# untitled.net
KiCad netlist of a schematic drawn in EAGLE
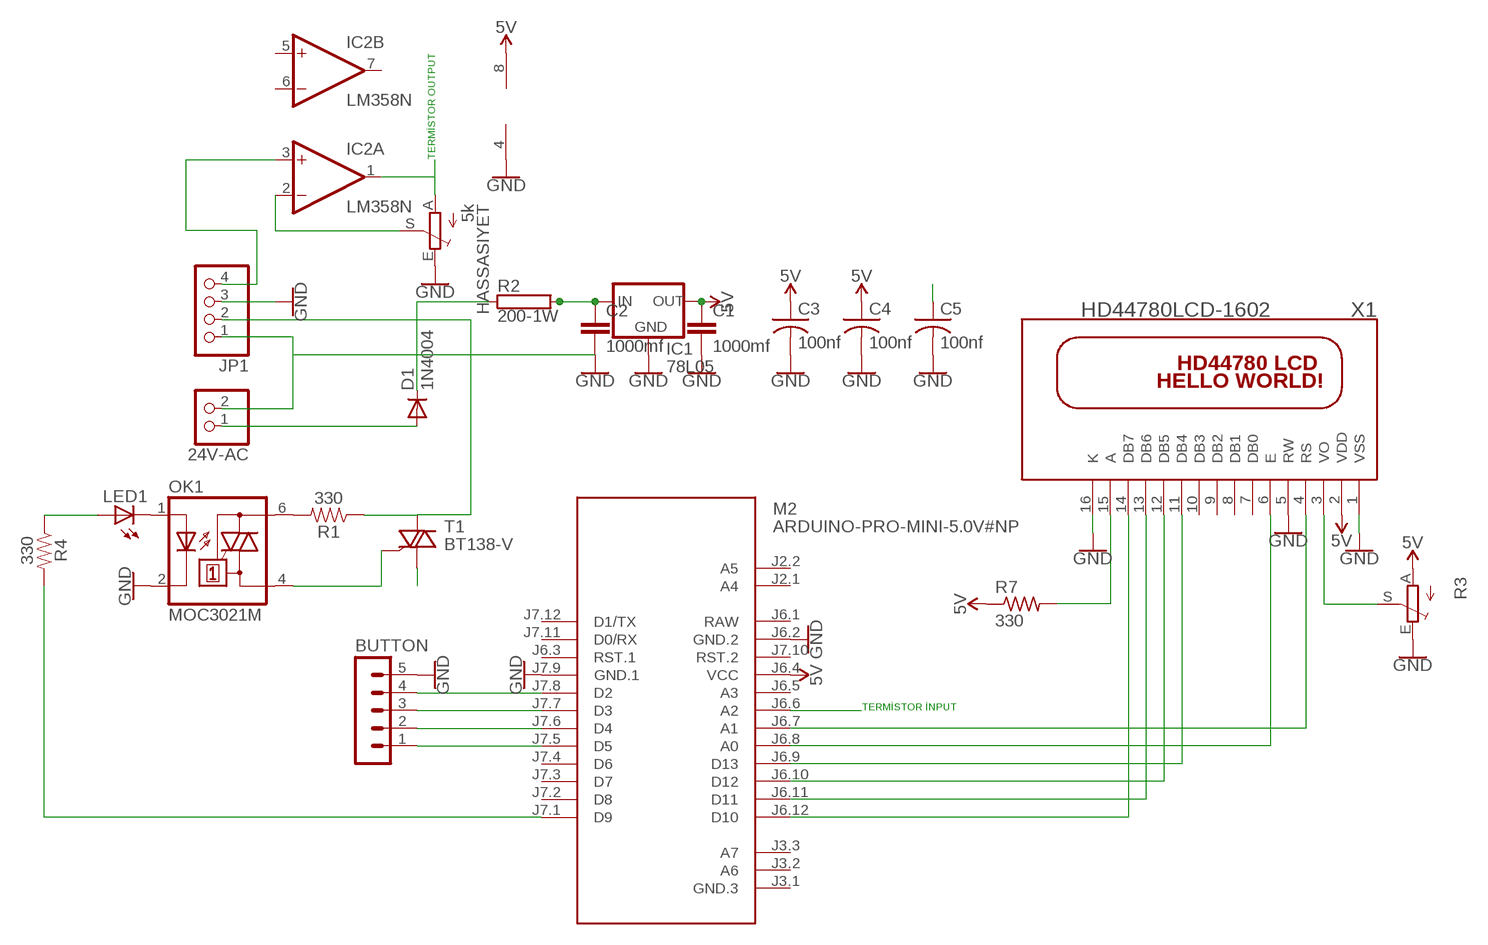
[diagram p0: schematic, sheet 1]

(export (version "E")
  (design (tool "Eeschema 10.0.6"))
  (components
    (comp (ref "24V-AC")
      (value "PINHD-1X2")
      (footprint "eagle-import:1X02")
      (libsource (lib "eagle-import") (part "PINHD-1X2"))
    )
    (comp (ref "BUTTON")
      (value "MA05-1")
      (footprint "eagle-import:MA05-1")
      (libsource (lib "eagle-import") (part "MA05-1"))
    )
    (comp (ref "C1")
      (value "1000mf")
      (footprint "eagle-import:C5B3.5")
      (libsource (lib "eagle-import") (part "C5/3.5"))
    )
    (comp (ref "C2")
      (value "1000mf")
      (footprint "eagle-import:C5B3.5")
      (libsource (lib "eagle-import") (part "C5/3.5"))
    )
    (comp (ref "C3")
      (value "100nf")
      (footprint "eagle-import:C1206")
      (libsource (lib "eagle-import") (part "C-USC1206"))
    )
    (comp (ref "C4")
      (value "100nf")
      (footprint "eagle-import:C1206")
      (libsource (lib "eagle-import") (part "C-USC1206"))
    )
    (comp (ref "C5")
      (value "100nf")
      (footprint "eagle-import:C1206")
      (libsource (lib "eagle-import") (part "C-USC1206"))
    )
    (comp (ref "D1")
      (value "1N4004")
      (footprint "eagle-import:DO41-10")
      (libsource (lib "eagle-import") (part "1N4004"))
    )
    (comp (ref "HASSASIYET")
      (value "5k")
      (footprint "eagle-import:S64W")
      (libsource (lib "eagle-import") (part "TRIM_EU-S64W"))
    )
    (comp (ref "IC1")
      (value "78L05")
      (footprint "eagle-import:78MXXS")
      (libsource (lib "eagle-import") (part "78MXXS"))
    )
    (comp (ref "IC2")
      (value "LM358N")
      (footprint "eagle-import:DIL08")
      (libsource (lib "eagle-import") (part "LM358N"))
    )
    (comp (ref "JP1")
      (value "PINHD-1X4")
      (footprint "eagle-import:1X04")
      (libsource (lib "eagle-import") (part "PINHD-1X4"))
    )
    (comp (ref "LED1")
      (value "LED3MM")
      (footprint "eagle-import:LED3MM")
      (libsource (lib "eagle-import") (part "LED3MM"))
    )
    (comp (ref "M2")
      (value "ARDUINO-PRO-MINI-5.0V#NP")
      (footprint "eagle-import:ARDUINO-PRO-MINI#NP")
      (libsource (lib "eagle-import") (part "ARDUINO-PRO-MINI-#NP5.0V"))
    )
    (comp (ref "OK1")
      (value "MOC3021M")
      (footprint "eagle-import:DIL06")
      (fields (field (name "MF") "FAIRCHILD SEMICONDUCTOR") (field (name "MPN") "MOC3021-M"))
      (libsource (lib "eagle-import") (part "MOC30M21"))
    )
    (comp (ref "R1")
      (value "330")
      (footprint "eagle-import:AXIAL-0.3")
      (libsource (lib "eagle-import") (part "1KOHM-HORIZ-1/4W-1%"))
    )
    (comp (ref "R2")
      (value "200-1W")
      (footprint "eagle-import:KH206-8R")
      (libsource (lib "eagle-import") (part "RKH206-8R"))
    )
    (comp (ref "R3")
      (value "TRIM_EU-CA6V")
      (footprint "eagle-import:CA6V")
      (libsource (lib "eagle-import") (part "TRIM_EU-CA6V"))
    )
    (comp (ref "R4")
      (value "330")
      (footprint "eagle-import:AXIAL-0.3")
      (libsource (lib "eagle-import") (part "1KOHM-HORIZ-1/4W-1%"))
    )
    (comp (ref "R7")
      (value "330")
      (footprint "eagle-import:0207_10")
      (libsource (lib "eagle-import") (part "R-US_0207/10"))
    )
    (comp (ref "T1")
      (value "BT138-V")
      (footprint "eagle-import:TO220BV")
      (libsource (lib "eagle-import") (part "BT138-V"))
    )
    (comp (ref "X1")
      (value "HD44780LCD-1602")
      (footprint "eagle-import:LCD1602")
      (libsource (lib "eagle-import") (part "HD44780LCD-1602"))
    )
  )
  (nets
    (net (code "1") (name "/24V") (class "Default")
      (node (ref "C2") (pin "1") (pinfunction "1_1") (pintype "passive"))
      (node (ref "C5") (pin "1") (pinfunction "1_1") (pintype "passive"))
      (node (ref "IC1") (pin "IN") (pinfunction "IN_IN") (pintype "input"))
      (node (ref "R2") (pin "2") (pinfunction "2_2") (pintype "passive"))
    )
    (net (code "2") (name "/A2") (class "Default")
      (node (ref "HASSASIYET") (pin "A") (pinfunction "A_A") (pintype "passive"))
      (node (ref "IC2") (pin "1") (pinfunction "OUT_1") (pintype "output"))
      (node (ref "M2") (pin "J6.6") (pinfunction "A2_J6.6") (pintype "bidirectional"))
    )
    (net (code "3") (name "/N$24") (class "Default")
      (node (ref "24V-AC") (pin "1") (pinfunction "1_1") (pintype "passive"))
      (node (ref "D1") (pin "A") (pinfunction "A_A") (pintype "passive"))
      (node (ref "T1") (pin "T1") (pinfunction "A1_T1") (pintype "passive"))
    )
    (net (code "4") (name "/RAW") (class "Default")
      (node (ref "M2") (pin "J6.1") (pinfunction "RAW_J6.1") (pintype "power_in"))
    )
    (net (code "5") (name "5V") (class "Default")
      (node (ref "C1") (pin "1") (pinfunction "1_1") (pintype "passive"))
      (node (ref "C3") (pin "1") (pinfunction "1_1") (pintype "passive"))
      (node (ref "C4") (pin "1") (pinfunction "1_1") (pintype "passive"))
      (node (ref "IC1") (pin "OUT") (pinfunction "OUT_OUT") (pintype "passive"))
      (node (ref "IC2") (pin "8") (pinfunction "V+_8") (pintype "power_in"))
      (node (ref "M2") (pin "J6.4") (pinfunction "VCC_J6.4") (pintype "power_in"))
      (node (ref "R3") (pin "A") (pinfunction "A_A") (pintype "passive"))
      (node (ref "R7") (pin "1") (pinfunction "1_1") (pintype "passive"))
      (node (ref "X1") (pin "2") (pinfunction "VDD_2") (pintype "power_in"))
    )
    (net (code "6") (name "GND") (class "Default")
      (node (ref "24V-AC") (pin "2") (pinfunction "2_2") (pintype "passive"))
      (node (ref "BUTTON") (pin "5") (pinfunction "5_5") (pintype "passive"))
      (node (ref "C1") (pin "2") (pinfunction "2_2") (pintype "passive"))
      (node (ref "C2") (pin "2") (pinfunction "2_2") (pintype "passive"))
      (node (ref "C3") (pin "2") (pinfunction "2_2") (pintype "passive"))
      (node (ref "C4") (pin "2") (pinfunction "2_2") (pintype "passive"))
      (node (ref "C5") (pin "2") (pinfunction "2_2") (pintype "passive"))
      (node (ref "HASSASIYET") (pin "E") (pinfunction "E_E") (pintype "passive"))
      (node (ref "IC1") (pin "GND") (pinfunction "GND_GND") (pintype "input"))
      (node (ref "IC2") (pin "4") (pinfunction "V-_4") (pintype "power_in"))
      (node (ref "JP1") (pin "1") (pinfunction "1_1") (pintype "passive"))
      (node (ref "JP1") (pin "3") (pinfunction "3_3") (pintype "passive"))
      (node (ref "M2") (pin "J6.2") (pinfunction "GND.2_J6.2") (pintype "power_in"))
      (node (ref "M2") (pin "J7.9") (pinfunction "GND.1_J7.9") (pintype "power_in"))
      (node (ref "OK1") (pin "2") (pinfunction "C_2") (pintype "passive"))
      (node (ref "R3") (pin "E") (pinfunction "E_E") (pintype "passive"))
      (node (ref "X1") (pin "1") (pinfunction "VSS_1") (pintype "power_in"))
      (node (ref "X1") (pin "16") (pinfunction "K_16") (pintype "input"))
      (node (ref "X1") (pin "5") (pinfunction "RW_5") (pintype "input"))
    )
    (net (code "7") (name "Net-(D1-PadC)") (class "Default")
      (node (ref "D1") (pin "C") (pinfunction "C_C") (pintype "passive"))
      (node (ref "R2") (pin "1") (pinfunction "1_1") (pintype "passive"))
    )
    (net (code "8") (name "Net-(IC2A-+IN)") (class "Default")
      (node (ref "IC2") (pin "3") (pinfunction "+IN_3") (pintype "input"))
      (node (ref "JP1") (pin "4") (pinfunction "4_4") (pintype "passive"))
    )
    (net (code "9") (name "Net-(IC2A--IN)") (class "Default")
      (node (ref "HASSASIYET") (pin "S") (pinfunction "S_S") (pintype "passive"))
      (node (ref "IC2") (pin "2") (pinfunction "-IN_2") (pintype "input"))
    )
    (net (code "10") (name "Net-(LED1-C)") (class "Default")
      (node (ref "LED1") (pin "K") (pinfunction "C_K") (pintype "passive"))
      (node (ref "OK1") (pin "1") (pinfunction "A_1") (pintype "passive"))
    )
    (net (code "11") (name "Net-(M2-A0)") (class "Default")
      (node (ref "M2") (pin "J6.8") (pinfunction "A0_J6.8") (pintype "bidirectional"))
      (node (ref "X1") (pin "6") (pinfunction "E_6") (pintype "input"))
    )
    (net (code "12") (name "Net-(M2-A1)") (class "Default")
      (node (ref "M2") (pin "J6.7") (pinfunction "A1_J6.7") (pintype "bidirectional"))
      (node (ref "X1") (pin "4") (pinfunction "RS_4") (pintype "input"))
    )
    (net (code "13") (name "Net-(M2-D2)") (class "Default")
      (node (ref "BUTTON") (pin "4") (pinfunction "4_4") (pintype "passive"))
      (node (ref "M2") (pin "J7.8") (pinfunction "D2_J7.8") (pintype "bidirectional"))
    )
    (net (code "14") (name "Net-(M2-D3)") (class "Default")
      (node (ref "BUTTON") (pin "3") (pinfunction "3_3") (pintype "passive"))
      (node (ref "M2") (pin "J7.7") (pinfunction "D3_J7.7") (pintype "bidirectional"))
    )
    (net (code "15") (name "Net-(M2-D4)") (class "Default")
      (node (ref "BUTTON") (pin "2") (pinfunction "2_2") (pintype "passive"))
      (node (ref "M2") (pin "J7.6") (pinfunction "D4_J7.6") (pintype "bidirectional"))
    )
    (net (code "16") (name "Net-(M2-D5)") (class "Default")
      (node (ref "BUTTON") (pin "1") (pinfunction "1_1") (pintype "passive"))
      (node (ref "M2") (pin "J7.5") (pinfunction "D5_J7.5") (pintype "bidirectional"))
    )
    (net (code "17") (name "Net-(M2-D9)") (class "Default")
      (node (ref "M2") (pin "J7.1") (pinfunction "D9_J7.1") (pintype "bidirectional"))
      (node (ref "R4") (pin "P$2") (pinfunction "2_P$2") (pintype "passive"))
    )
    (net (code "18") (name "Net-(M2-D10)") (class "Default")
      (node (ref "M2") (pin "J6.12") (pinfunction "D10_J6.12") (pintype "bidirectional"))
      (node (ref "X1") (pin "14") (pinfunction "DB7_14") (pintype "bidirectional"))
    )
    (net (code "19") (name "Net-(M2-D11)") (class "Default")
      (node (ref "M2") (pin "J6.11") (pinfunction "D11_J6.11") (pintype "bidirectional"))
      (node (ref "X1") (pin "13") (pinfunction "DB6_13") (pintype "bidirectional"))
    )
    (net (code "20") (name "Net-(M2-D12)") (class "Default")
      (node (ref "M2") (pin "J6.10") (pinfunction "D12_J6.10") (pintype "bidirectional"))
      (node (ref "X1") (pin "12") (pinfunction "DB5_12") (pintype "bidirectional"))
    )
    (net (code "21") (name "Net-(M2-D13)") (class "Default")
      (node (ref "M2") (pin "J6.9") (pinfunction "D13_J6.9") (pintype "bidirectional"))
      (node (ref "X1") (pin "11") (pinfunction "DB4_11") (pintype "bidirectional"))
    )
    (net (code "22") (name "Net-(OK1-A1)") (class "Default")
      (node (ref "OK1") (pin "4") (pinfunction "A1_4") (pintype "passive"))
      (node (ref "T1") (pin "G") (pinfunction "G_G") (pintype "passive"))
    )
    (net (code "23") (name "Net-(OK1-A2)") (class "Default")
      (node (ref "OK1") (pin "6") (pinfunction "A2_6") (pintype "passive"))
      (node (ref "R1") (pin "P$2") (pinfunction "2_P$2") (pintype "passive"))
    )
    (net (code "24") (name "Net-(R1-1)") (class "Default")
      (node (ref "JP1") (pin "2") (pinfunction "2_2") (pintype "passive"))
      (node (ref "R1") (pin "P$1") (pinfunction "1_P$1") (pintype "passive"))
      (node (ref "T1") (pin "T2") (pinfunction "A2_T2") (pintype "passive"))
    )
    (net (code "25") (name "Net-(R4-1)") (class "Default")
      (node (ref "LED1") (pin "A") (pinfunction "A_A") (pintype "passive"))
      (node (ref "R4") (pin "P$1") (pinfunction "1_P$1") (pintype "passive"))
    )
    (net (code "26") (name "Net-(X1-A)") (class "Default")
      (node (ref "R7") (pin "2") (pinfunction "2_2") (pintype "passive"))
      (node (ref "X1") (pin "15") (pinfunction "A_15") (pintype "input"))
    )
    (net (code "27") (name "Net-(X1-VO)") (class "Default")
      (node (ref "R3") (pin "S") (pinfunction "S_S") (pintype "passive"))
      (node (ref "X1") (pin "3") (pinfunction "VO_3") (pintype "input"))
    )
    (net (code "28") (name "unconnected-(IC2B-+IN-Pad5)") (class "Default")
      (node (ref "IC2") (pin "5") (pinfunction "+IN_5") (pintype "input"))
    )
    (net (code "29") (name "unconnected-(IC2B--IN-Pad6)") (class "Default")
      (node (ref "IC2") (pin "6") (pinfunction "-IN_6") (pintype "input"))
    )
    (net (code "30") (name "unconnected-(IC2B-OUT-Pad7)") (class "Default")
      (node (ref "IC2") (pin "7") (pinfunction "OUT_7") (pintype "output"))
    )
    (net (code "31") (name "unconnected-(M2-A3-PadJ6.5)") (class "Default")
      (node (ref "M2") (pin "J6.5") (pinfunction "A3_J6.5") (pintype "bidirectional"))
    )
    (net (code "32") (name "unconnected-(M2-A4-PadJ2.1)") (class "Default")
      (node (ref "M2") (pin "J2.1") (pinfunction "A4_J2.1") (pintype "bidirectional"))
    )
    (net (code "33") (name "unconnected-(M2-A5-PadJ2.2)") (class "Default")
      (node (ref "M2") (pin "J2.2") (pinfunction "A5_J2.2") (pintype "bidirectional"))
    )
    (net (code "34") (name "unconnected-(M2-A6-PadJ3.2)") (class "Default")
      (node (ref "M2") (pin "J3.2") (pinfunction "A6_J3.2") (pintype "bidirectional"))
    )
    (net (code "35") (name "unconnected-(M2-A7-PadJ3.3)") (class "Default")
      (node (ref "M2") (pin "J3.3") (pinfunction "A7_J3.3") (pintype "bidirectional"))
    )
    (net (code "36") (name "unconnected-(M2-D0{slash}RX-PadJ7.11)") (class "Default")
      (node (ref "M2") (pin "J7.11") (pinfunction "D0/RX_J7.11") (pintype "bidirectional"))
    )
    (net (code "37") (name "unconnected-(M2-D1{slash}TX-PadJ7.12)") (class "Default")
      (node (ref "M2") (pin "J7.12") (pinfunction "D1/TX_J7.12") (pintype "bidirectional"))
    )
    (net (code "38") (name "unconnected-(M2-D6-PadJ7.4)") (class "Default")
      (node (ref "M2") (pin "J7.4") (pinfunction "D6_J7.4") (pintype "bidirectional"))
    )
    (net (code "39") (name "unconnected-(M2-D7-PadJ7.3)") (class "Default")
      (node (ref "M2") (pin "J7.3") (pinfunction "D7_J7.3") (pintype "bidirectional"))
    )
    (net (code "40") (name "unconnected-(M2-D8-PadJ7.2)") (class "Default")
      (node (ref "M2") (pin "J7.2") (pinfunction "D8_J7.2") (pintype "bidirectional"))
    )
    (net (code "41") (name "unconnected-(M2-GND.3-PadJ3.1)") (class "Default")
      (node (ref "M2") (pin "J3.1") (pinfunction "GND.3_J3.1") (pintype "bidirectional"))
    )
    (net (code "42") (name "unconnected-(M2-RST.1-PadJ6.3)") (class "Default")
      (node (ref "M2") (pin "J6.3") (pinfunction "RST.1_J6.3") (pintype "bidirectional"))
    )
    (net (code "43") (name "unconnected-(M2-RST.2-PadJ7.10)") (class "Default")
      (node (ref "M2") (pin "J7.10") (pinfunction "RST.2_J7.10") (pintype "bidirectional"))
    )
    (net (code "44") (name "unconnected-(X1-DB0-Pad7)") (class "Default")
      (node (ref "X1") (pin "7") (pinfunction "DB0_7") (pintype "bidirectional"))
    )
    (net (code "45") (name "unconnected-(X1-DB1-Pad8)") (class "Default")
      (node (ref "X1") (pin "8") (pinfunction "DB1_8") (pintype "bidirectional"))
    )
    (net (code "46") (name "unconnected-(X1-DB2-Pad9)") (class "Default")
      (node (ref "X1") (pin "9") (pinfunction "DB2_9") (pintype "bidirectional"))
    )
    (net (code "47") (name "unconnected-(X1-DB3-Pad10)") (class "Default")
      (node (ref "X1") (pin "10") (pinfunction "DB3_10") (pintype "bidirectional"))
    )
  )
)
